# cowsynth_teensy_breakout_revA.net
KiCad netlist of a schematic drawn in EAGLE
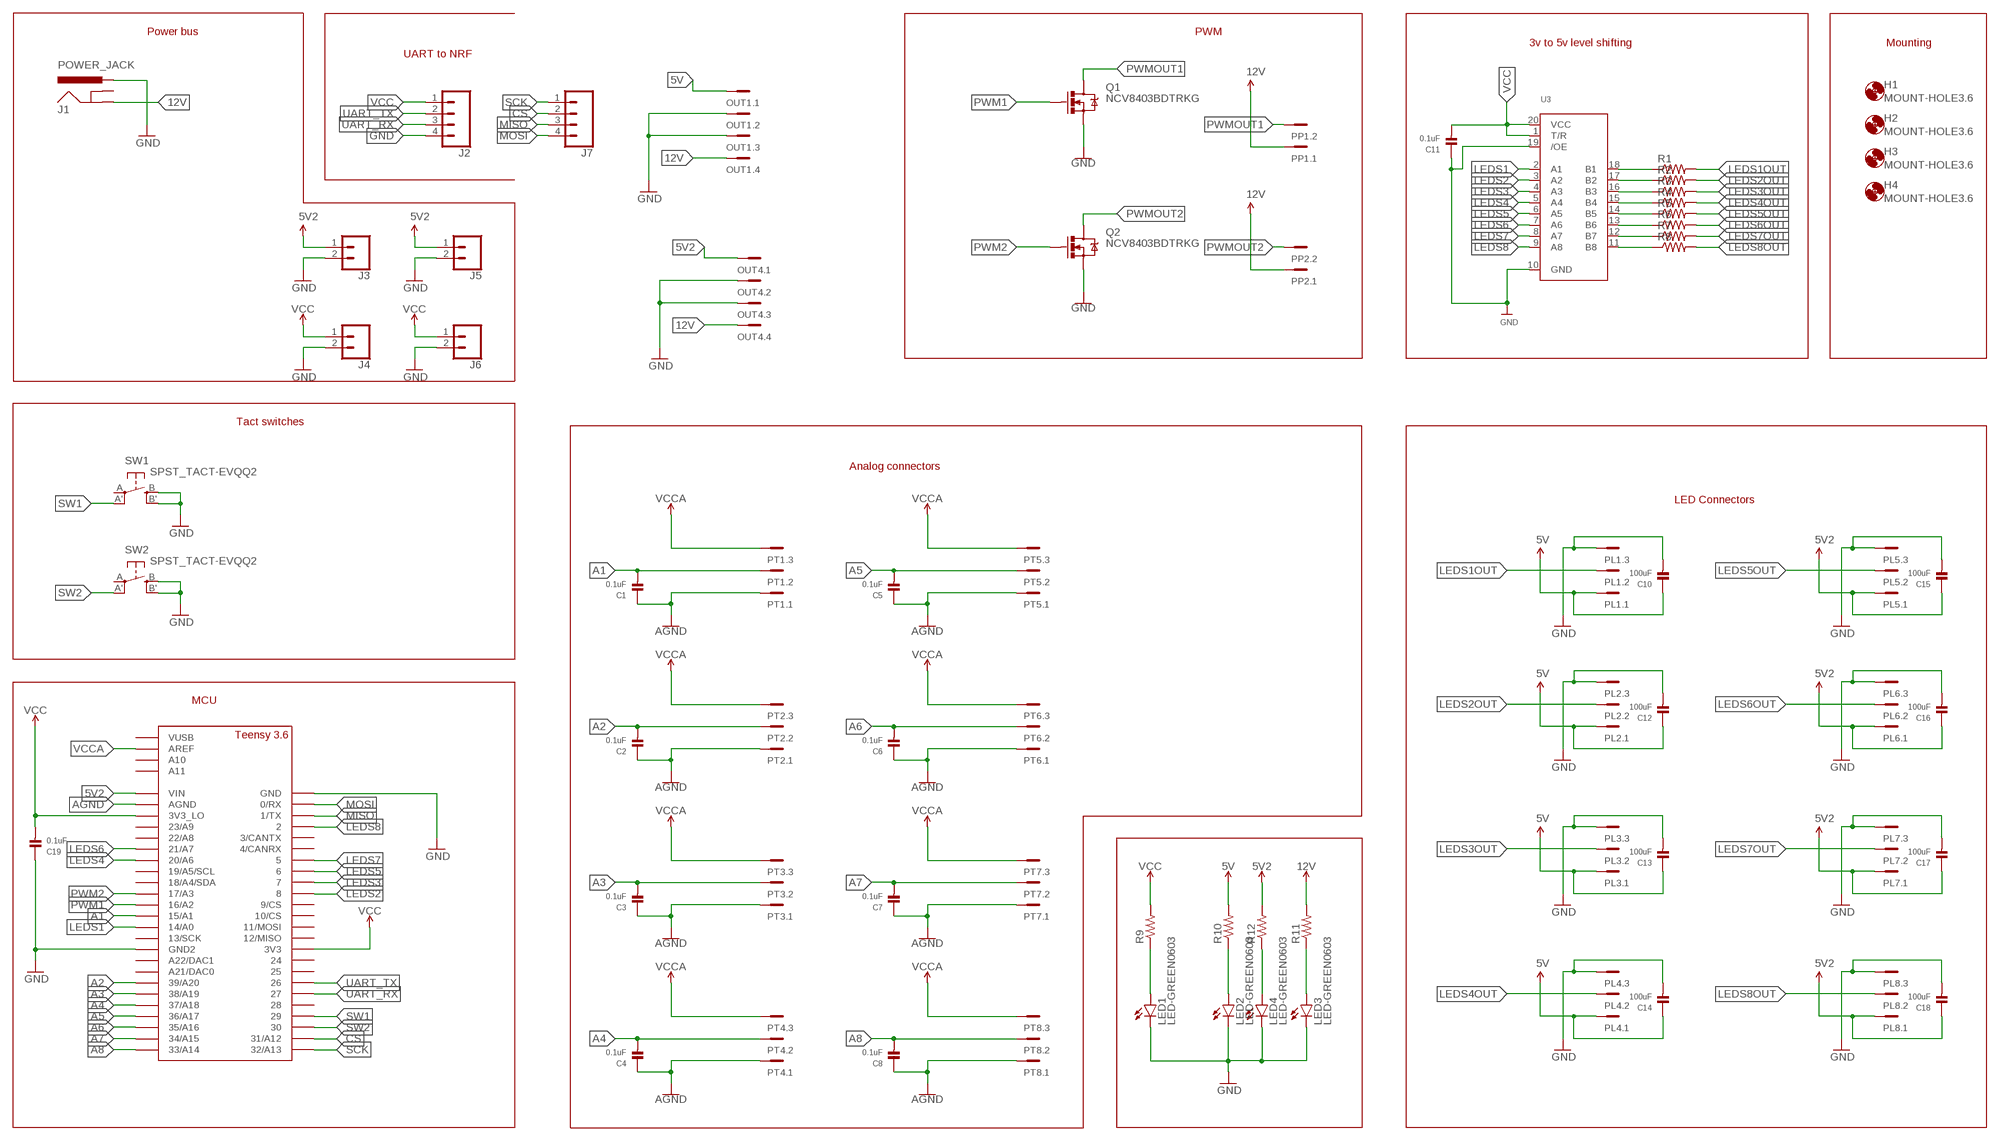
[diagram p0: schematic, sheet 1]

(export (version "E")
  (design (tool "Eeschema 10.0.6"))
  (components
    (comp (ref "C1")
      (value "0.1uF")
      (footprint "eagle-import:0603")
      (libsource (lib "eagle-import") (part "CAP_CERAMIC0603"))
    )
    (comp (ref "C2")
      (value "0.1uF")
      (footprint "eagle-import:0603")
      (libsource (lib "eagle-import") (part "CAP_CERAMIC0603"))
    )
    (comp (ref "C3")
      (value "0.1uF")
      (footprint "eagle-import:0603")
      (libsource (lib "eagle-import") (part "CAP_CERAMIC0603"))
    )
    (comp (ref "C4")
      (value "0.1uF")
      (footprint "eagle-import:0603")
      (libsource (lib "eagle-import") (part "CAP_CERAMIC0603"))
    )
    (comp (ref "C5")
      (value "0.1uF")
      (footprint "eagle-import:0603")
      (libsource (lib "eagle-import") (part "CAP_CERAMIC0603"))
    )
    (comp (ref "C6")
      (value "0.1uF")
      (footprint "eagle-import:0603")
      (libsource (lib "eagle-import") (part "CAP_CERAMIC0603"))
    )
    (comp (ref "C7")
      (value "0.1uF")
      (footprint "eagle-import:0603")
      (libsource (lib "eagle-import") (part "CAP_CERAMIC0603"))
    )
    (comp (ref "C8")
      (value "0.1uF")
      (footprint "eagle-import:0603")
      (libsource (lib "eagle-import") (part "CAP_CERAMIC0603"))
    )
    (comp (ref "C10")
      (value "100uF")
      (footprint "eagle-import:1206")
      (libsource (lib "eagle-import") (part "CAP_CERAMIC1206"))
    )
    (comp (ref "C11")
      (value "0.1uF")
      (footprint "eagle-import:0603")
      (libsource (lib "eagle-import") (part "CAP_CERAMIC0603"))
    )
    (comp (ref "C12")
      (value "100uF")
      (footprint "eagle-import:1206")
      (libsource (lib "eagle-import") (part "CAP_CERAMIC1206"))
    )
    (comp (ref "C13")
      (value "100uF")
      (footprint "eagle-import:1206")
      (libsource (lib "eagle-import") (part "CAP_CERAMIC1206"))
    )
    (comp (ref "C14")
      (value "100uF")
      (footprint "eagle-import:1206")
      (libsource (lib "eagle-import") (part "CAP_CERAMIC1206"))
    )
    (comp (ref "C15")
      (value "100uF")
      (footprint "eagle-import:1206")
      (libsource (lib "eagle-import") (part "CAP_CERAMIC1206"))
    )
    (comp (ref "C16")
      (value "100uF")
      (footprint "eagle-import:1206")
      (libsource (lib "eagle-import") (part "CAP_CERAMIC1206"))
    )
    (comp (ref "C17")
      (value "100uF")
      (footprint "eagle-import:1206")
      (libsource (lib "eagle-import") (part "CAP_CERAMIC1206"))
    )
    (comp (ref "C18")
      (value "100uF")
      (footprint "eagle-import:1206")
      (libsource (lib "eagle-import") (part "CAP_CERAMIC1206"))
    )
    (comp (ref "C19")
      (value "0.1uF")
      (footprint "eagle-import:0603")
      (libsource (lib "eagle-import") (part "CAP_CERAMIC0603"))
    )
    (comp (ref "H1")
      (value "MOUNT-HOLE3.6")
      (footprint "eagle-import:3,6")
      (libsource (lib "eagle-import") (part "MOUNT-HOLE3.6"))
    )
    (comp (ref "H2")
      (value "MOUNT-HOLE3.6")
      (footprint "eagle-import:3,6")
      (libsource (lib "eagle-import") (part "MOUNT-HOLE3.6"))
    )
    (comp (ref "H3")
      (value "MOUNT-HOLE3.6")
      (footprint "eagle-import:3,6")
      (libsource (lib "eagle-import") (part "MOUNT-HOLE3.6"))
    )
    (comp (ref "H4")
      (value "MOUNT-HOLE3.6")
      (footprint "eagle-import:3,6")
      (libsource (lib "eagle-import") (part "MOUNT-HOLE3.6"))
    )
    (comp (ref "J1")
      (value "POWER_JACK")
      (footprint "eagle-import:POWER_JACK_PTH")
      (libsource (lib "eagle-import") (part "POWER_JACK"))
    )
    (comp (ref "J2")
      (value "CONN_04")
      (footprint "eagle-import:1X04")
      (libsource (lib "eagle-import") (part "CONN_04"))
    )
    (comp (ref "J3")
      (value "CONN_02")
      (footprint "eagle-import:1X02")
      (libsource (lib "eagle-import") (part "CONN_02"))
    )
    (comp (ref "J4")
      (value "CONN_02")
      (footprint "eagle-import:1X02")
      (libsource (lib "eagle-import") (part "CONN_02"))
    )
    (comp (ref "J5")
      (value "CONN_02")
      (footprint "eagle-import:1X02")
      (libsource (lib "eagle-import") (part "CONN_02"))
    )
    (comp (ref "J6")
      (value "CONN_02")
      (footprint "eagle-import:1X02")
      (libsource (lib "eagle-import") (part "CONN_02"))
    )
    (comp (ref "J7")
      (value "CONN_04")
      (footprint "eagle-import:1X04")
      (libsource (lib "eagle-import") (part "CONN_04"))
    )
    (comp (ref "LED1")
      (value "LED-GREEN0603")
      (footprint "eagle-import:0603-GREEN")
      (libsource (lib "eagle-import") (part "LED-GREEN0603"))
    )
    (comp (ref "LED2")
      (value "LED-GREEN0603")
      (footprint "eagle-import:0603-GREEN")
      (libsource (lib "eagle-import") (part "LED-GREEN0603"))
    )
    (comp (ref "LED3")
      (value "LED-GREEN0603")
      (footprint "eagle-import:0603-GREEN")
      (libsource (lib "eagle-import") (part "LED-GREEN0603"))
    )
    (comp (ref "LED4")
      (value "LED-GREEN0603")
      (footprint "eagle-import:0603-GREEN")
      (libsource (lib "eagle-import") (part "LED-GREEN0603"))
    )
    (comp (ref "OUT1")
      (value "MC4")
      (footprint "eagle-import:MC4")
      (libsource (lib "eagle-import") (part "MC4"))
    )
    (comp (ref "OUT4")
      (value "MC4")
      (footprint "eagle-import:MC4")
      (libsource (lib "eagle-import") (part "MC4"))
    )
    (comp (ref "PL1")
      (value "MC3")
      (footprint "eagle-import:MC3")
      (libsource (lib "eagle-import") (part "MC3"))
    )
    (comp (ref "PL2")
      (value "MC3")
      (footprint "eagle-import:MC3")
      (libsource (lib "eagle-import") (part "MC3"))
    )
    (comp (ref "PL3")
      (value "MC3")
      (footprint "eagle-import:MC3")
      (libsource (lib "eagle-import") (part "MC3"))
    )
    (comp (ref "PL4")
      (value "MC3")
      (footprint "eagle-import:MC3")
      (libsource (lib "eagle-import") (part "MC3"))
    )
    (comp (ref "PL5")
      (value "MC3")
      (footprint "eagle-import:MC3")
      (libsource (lib "eagle-import") (part "MC3"))
    )
    (comp (ref "PL6")
      (value "MC3")
      (footprint "eagle-import:MC3")
      (libsource (lib "eagle-import") (part "MC3"))
    )
    (comp (ref "PL7")
      (value "MC3")
      (footprint "eagle-import:MC3")
      (libsource (lib "eagle-import") (part "MC3"))
    )
    (comp (ref "PL8")
      (value "MC3")
      (footprint "eagle-import:MC3")
      (libsource (lib "eagle-import") (part "MC3"))
    )
    (comp (ref "PP1")
      (value "MC2")
      (footprint "eagle-import:MC2")
      (libsource (lib "eagle-import") (part "MC2"))
    )
    (comp (ref "PP2")
      (value "MC2")
      (footprint "eagle-import:MC2")
      (libsource (lib "eagle-import") (part "MC2"))
    )
    (comp (ref "PT1")
      (value "MC3")
      (footprint "eagle-import:MC3")
      (libsource (lib "eagle-import") (part "MC3"))
    )
    (comp (ref "PT2")
      (value "MC3")
      (footprint "eagle-import:MC3")
      (libsource (lib "eagle-import") (part "MC3"))
    )
    (comp (ref "PT3")
      (value "MC3")
      (footprint "eagle-import:MC3")
      (libsource (lib "eagle-import") (part "MC3"))
    )
    (comp (ref "PT4")
      (value "MC3")
      (footprint "eagle-import:MC3")
      (libsource (lib "eagle-import") (part "MC3"))
    )
    (comp (ref "PT5")
      (value "MC3")
      (footprint "eagle-import:MC3")
      (libsource (lib "eagle-import") (part "MC3"))
    )
    (comp (ref "PT6")
      (value "MC3")
      (footprint "eagle-import:MC3")
      (libsource (lib "eagle-import") (part "MC3"))
    )
    (comp (ref "PT7")
      (value "MC3")
      (footprint "eagle-import:MC3")
      (libsource (lib "eagle-import") (part "MC3"))
    )
    (comp (ref "PT8")
      (value "MC3")
      (footprint "eagle-import:MC3")
      (libsource (lib "eagle-import") (part "MC3"))
    )
    (comp (ref "Q1")
      (value "NCV8403BDTRKG")
      (footprint "eagle-import:DPAK")
      (libsource (lib "eagle-import") (part "MOSFET-NCHANNELFDD8780"))
    )
    (comp (ref "Q2")
      (value "NCV8403BDTRKG")
      (footprint "eagle-import:DPAK")
      (libsource (lib "eagle-import") (part "MOSFET-NCHANNELFDD8780"))
    )
    (comp (ref "R1")
      (value "R-US_R0603")
      (footprint "eagle-import:R0603")
      (libsource (lib "eagle-import") (part "R-US_R0603"))
    )
    (comp (ref "R2")
      (value "R-US_R0603")
      (footprint "eagle-import:R0603")
      (libsource (lib "eagle-import") (part "R-US_R0603"))
    )
    (comp (ref "R3")
      (value "R-US_R0603")
      (footprint "eagle-import:R0603")
      (libsource (lib "eagle-import") (part "R-US_R0603"))
    )
    (comp (ref "R4")
      (value "R-US_R0603")
      (footprint "eagle-import:R0603")
      (libsource (lib "eagle-import") (part "R-US_R0603"))
    )
    (comp (ref "R5")
      (value "R-US_R0603")
      (footprint "eagle-import:R0603")
      (libsource (lib "eagle-import") (part "R-US_R0603"))
    )
    (comp (ref "R6")
      (value "R-US_R0603")
      (footprint "eagle-import:R0603")
      (libsource (lib "eagle-import") (part "R-US_R0603"))
    )
    (comp (ref "R7")
      (value "R-US_R0603")
      (footprint "eagle-import:R0603")
      (libsource (lib "eagle-import") (part "R-US_R0603"))
    )
    (comp (ref "R8")
      (value "R-US_R0603")
      (footprint "eagle-import:R0603")
      (libsource (lib "eagle-import") (part "R-US_R0603"))
    )
    (comp (ref "R9")
      (value "R-US_R0603")
      (footprint "eagle-import:R0603")
      (libsource (lib "eagle-import") (part "R-US_R0603"))
    )
    (comp (ref "R10")
      (value "R-US_R0603")
      (footprint "eagle-import:R0603")
      (libsource (lib "eagle-import") (part "R-US_R0603"))
    )
    (comp (ref "R11")
      (value "R-US_R0603")
      (footprint "eagle-import:R0603")
      (libsource (lib "eagle-import") (part "R-US_R0603"))
    )
    (comp (ref "R12")
      (value "R-US_R0603")
      (footprint "eagle-import:R0603")
      (libsource (lib "eagle-import") (part "R-US_R0603"))
    )
    (comp (ref "SW1")
      (value "SPST_TACT-EVQQ2")
      (footprint "eagle-import:EVQ-Q2")
      (libsource (lib "eagle-import") (part "SPST_TACT-EVQQ2"))
    )
    (comp (ref "SW2")
      (value "SPST_TACT-EVQQ2")
      (footprint "eagle-import:EVQ-Q2")
      (libsource (lib "eagle-import") (part "SPST_TACT-EVQQ2"))
    )
    (comp (ref "U$1")
      (value "TEENSY_3.5/3.6_BASIC")
      (footprint "eagle-import:TEENSY_3.5_3.6_BASIC")
      (libsource (lib "eagle-import") (part "TEENSY_3.5/3.6_BASIC"))
    )
    (comp (ref "U3")
      (value "74LCX245")
      (footprint "eagle-import:TSSOP20")
      (libsource (lib "eagle-import") (part "74LCX245"))
    )
  )
  (nets
    (net (code "1") (name "5V") (class "Default")
      (node (ref "C10") (pin "1") (pinfunction "P$1_1") (pintype "passive"))
      (node (ref "C12") (pin "1") (pinfunction "P$1_1") (pintype "passive"))
      (node (ref "C13") (pin "1") (pinfunction "P$1_1") (pintype "passive"))
      (node (ref "C14") (pin "1") (pinfunction "P$1_1") (pintype "passive"))
      (node (ref "OUT1") (pin "1") (pinfunction "SK_1") (pintype "passive"))
      (node (ref "PL1") (pin "1") (pinfunction "SK_1") (pintype "passive"))
      (node (ref "PL2") (pin "1") (pinfunction "SK_1") (pintype "passive"))
      (node (ref "PL3") (pin "1") (pinfunction "SK_1") (pintype "passive"))
      (node (ref "PL4") (pin "1") (pinfunction "SK_1") (pintype "passive"))
      (node (ref "R10") (pin "2") (pinfunction "2_2") (pintype "passive"))
    )
    (net (code "2") (name "5V2") (class "Default")
      (node (ref "C15") (pin "1") (pinfunction "P$1_1") (pintype "passive"))
      (node (ref "C16") (pin "1") (pinfunction "P$1_1") (pintype "passive"))
      (node (ref "C17") (pin "1") (pinfunction "P$1_1") (pintype "passive"))
      (node (ref "C18") (pin "1") (pinfunction "P$1_1") (pintype "passive"))
      (node (ref "J3") (pin "1") (pinfunction "1_1") (pintype "passive"))
      (node (ref "J5") (pin "1") (pinfunction "1_1") (pintype "passive"))
      (node (ref "OUT4") (pin "1") (pinfunction "SK_1") (pintype "passive"))
      (node (ref "PL5") (pin "1") (pinfunction "SK_1") (pintype "passive"))
      (node (ref "PL6") (pin "1") (pinfunction "SK_1") (pintype "passive"))
      (node (ref "PL7") (pin "1") (pinfunction "SK_1") (pintype "passive"))
      (node (ref "PL8") (pin "1") (pinfunction "SK_1") (pintype "passive"))
      (node (ref "R12") (pin "2") (pinfunction "2_2") (pintype "passive"))
      (node (ref "U$1") (pin "VIN") (pinfunction "VIN_VIN") (pintype "bidirectional"))
    )
    (net (code "3") (name "12V") (class "Default")
      (node (ref "J1") (pin "GND") (pinfunction "GND_GND") (pintype "bidirectional"))
      (node (ref "OUT1") (pin "4") (pinfunction "SK_4") (pintype "passive"))
      (node (ref "OUT4") (pin "4") (pinfunction "SK_4") (pintype "passive"))
      (node (ref "PP1") (pin "1") (pinfunction "SK_1") (pintype "passive"))
      (node (ref "PP2") (pin "1") (pinfunction "SK_1") (pintype "passive"))
      (node (ref "R11") (pin "2") (pinfunction "2_2") (pintype "passive"))
    )
    (net (code "4") (name "A1") (class "Default")
      (node (ref "C1") (pin "2") (pinfunction "P$2_2") (pintype "passive"))
      (node (ref "PT1") (pin "2") (pinfunction "SK_2") (pintype "passive"))
      (node (ref "U$1") (pin "15/A1") (pinfunction "15/A1_15/A1") (pintype "bidirectional"))
    )
    (net (code "5") (name "A2") (class "Default")
      (node (ref "C2") (pin "2") (pinfunction "P$2_2") (pintype "passive"))
      (node (ref "PT2") (pin "2") (pinfunction "SK_2") (pintype "passive"))
      (node (ref "U$1") (pin "39/A20") (pinfunction "39/A20_39/A20") (pintype "bidirectional"))
    )
    (net (code "6") (name "A3") (class "Default")
      (node (ref "C3") (pin "2") (pinfunction "P$2_2") (pintype "passive"))
      (node (ref "PT3") (pin "2") (pinfunction "SK_2") (pintype "passive"))
      (node (ref "U$1") (pin "38/A19") (pinfunction "38/A19_38/A19") (pintype "bidirectional"))
    )
    (net (code "7") (name "A4") (class "Default")
      (node (ref "C4") (pin "2") (pinfunction "P$2_2") (pintype "passive"))
      (node (ref "PT4") (pin "2") (pinfunction "SK_2") (pintype "passive"))
      (node (ref "U$1") (pin "37/A18") (pinfunction "37/A18_37/A18") (pintype "bidirectional"))
    )
    (net (code "8") (name "A5") (class "Default")
      (node (ref "C5") (pin "2") (pinfunction "P$2_2") (pintype "passive"))
      (node (ref "PT5") (pin "2") (pinfunction "SK_2") (pintype "passive"))
      (node (ref "U$1") (pin "36/A17") (pinfunction "36/A17_36/A17") (pintype "bidirectional"))
    )
    (net (code "9") (name "A6") (class "Default")
      (node (ref "C6") (pin "2") (pinfunction "P$2_2") (pintype "passive"))
      (node (ref "PT6") (pin "2") (pinfunction "SK_2") (pintype "passive"))
      (node (ref "U$1") (pin "35/A16") (pinfunction "35/A16_35/A16") (pintype "bidirectional"))
    )
    (net (code "10") (name "A7") (class "Default")
      (node (ref "C7") (pin "2") (pinfunction "P$2_2") (pintype "passive"))
      (node (ref "PT7") (pin "2") (pinfunction "SK_2") (pintype "passive"))
      (node (ref "U$1") (pin "34/A15") (pinfunction "34/A15_34/A15") (pintype "bidirectional"))
    )
    (net (code "11") (name "A8") (class "Default")
      (node (ref "C8") (pin "2") (pinfunction "P$2_2") (pintype "passive"))
      (node (ref "PT8") (pin "2") (pinfunction "SK_2") (pintype "passive"))
      (node (ref "U$1") (pin "33/A14") (pinfunction "33/A14_33/A14") (pintype "bidirectional"))
    )
    (net (code "12") (name "AGND") (class "Default")
      (node (ref "C1") (pin "1") (pinfunction "P$1_1") (pintype "passive"))
      (node (ref "C2") (pin "1") (pinfunction "P$1_1") (pintype "passive"))
      (node (ref "C3") (pin "1") (pinfunction "P$1_1") (pintype "passive"))
      (node (ref "C4") (pin "1") (pinfunction "P$1_1") (pintype "passive"))
      (node (ref "C5") (pin "1") (pinfunction "P$1_1") (pintype "passive"))
      (node (ref "C6") (pin "1") (pinfunction "P$1_1") (pintype "passive"))
      (node (ref "C7") (pin "1") (pinfunction "P$1_1") (pintype "passive"))
      (node (ref "C8") (pin "1") (pinfunction "P$1_1") (pintype "passive"))
      (node (ref "PT1") (pin "1") (pinfunction "SK_1") (pintype "passive"))
      (node (ref "PT2") (pin "1") (pinfunction "SK_1") (pintype "passive"))
      (node (ref "PT3") (pin "1") (pinfunction "SK_1") (pintype "passive"))
      (node (ref "PT4") (pin "1") (pinfunction "SK_1") (pintype "passive"))
      (node (ref "PT5") (pin "1") (pinfunction "SK_1") (pintype "passive"))
      (node (ref "PT6") (pin "1") (pinfunction "SK_1") (pintype "passive"))
      (node (ref "PT7") (pin "1") (pinfunction "SK_1") (pintype "passive"))
      (node (ref "PT8") (pin "1") (pinfunction "SK_1") (pintype "passive"))
      (node (ref "U$1") (pin "AGND") (pinfunction "AGND_AGND") (pintype "bidirectional"))
    )
    (net (code "13") (name "CS") (class "Default")
      (node (ref "J7") (pin "2") (pinfunction "2_2") (pintype "passive"))
      (node (ref "U$1") (pin "31/A12") (pinfunction "31/A12_31/A12") (pintype "bidirectional"))
    )
    (net (code "14") (name "GND") (class "Default")
      (node (ref "C10") (pin "2") (pinfunction "P$2_2") (pintype "passive"))
      (node (ref "C11") (pin "1") (pinfunction "P$1_1") (pintype "passive"))
      (node (ref "C12") (pin "2") (pinfunction "P$2_2") (pintype "passive"))
      (node (ref "C13") (pin "2") (pinfunction "P$2_2") (pintype "passive"))
      (node (ref "C14") (pin "2") (pinfunction "P$2_2") (pintype "passive"))
      (node (ref "C15") (pin "2") (pinfunction "P$2_2") (pintype "passive"))
      (node (ref "C16") (pin "2") (pinfunction "P$2_2") (pintype "passive"))
      (node (ref "C17") (pin "2") (pinfunction "P$2_2") (pintype "passive"))
      (node (ref "C18") (pin "2") (pinfunction "P$2_2") (pintype "passive"))
      (node (ref "C19") (pin "1") (pinfunction "P$1_1") (pintype "passive"))
      (node (ref "J1") (pin "PWR") (pinfunction "PWR_PWR") (pintype "bidirectional"))
      (node (ref "J2") (pin "4") (pinfunction "4_4") (pintype "passive"))
      (node (ref "J3") (pin "2") (pinfunction "2_2") (pintype "passive"))
      (node (ref "J4") (pin "2") (pinfunction "2_2") (pintype "passive"))
      (node (ref "J5") (pin "2") (pinfunction "2_2") (pintype "passive"))
      (node (ref "J6") (pin "2") (pinfunction "2_2") (pintype "passive"))
      (node (ref "LED1") (pin "C") (pinfunction "C_C") (pintype "passive"))
      (node (ref "LED2") (pin "C") (pinfunction "C_C") (pintype "passive"))
      (node (ref "LED3") (pin "C") (pinfunction "C_C") (pintype "passive"))
      (node (ref "LED4") (pin "C") (pinfunction "C_C") (pintype "passive"))
      (node (ref "OUT1") (pin "2") (pinfunction "SK_2") (pintype "passive"))
      (node (ref "OUT1") (pin "3") (pinfunction "SK_3") (pintype "passive"))
      (node (ref "OUT4") (pin "2") (pinfunction "SK_2") (pintype "passive"))
      (node (ref "OUT4") (pin "3") (pinfunction "SK_3") (pintype "passive"))
      (node (ref "PL1") (pin "3") (pinfunction "SK_3") (pintype "passive"))
      (node (ref "PL2") (pin "3") (pinfunction "SK_3") (pintype "passive"))
      (node (ref "PL3") (pin "3") (pinfunction "SK_3") (pintype "passive"))
      (node (ref "PL4") (pin "3") (pinfunction "SK_3") (pintype "passive"))
      (node (ref "PL5") (pin "3") (pinfunction "SK_3") (pintype "passive"))
      (node (ref "PL6") (pin "3") (pinfunction "SK_3") (pintype "passive"))
      (node (ref "PL7") (pin "3") (pinfunction "SK_3") (pintype "passive"))
      (node (ref "PL8") (pin "3") (pinfunction "SK_3") (pintype "passive"))
      (node (ref "Q1") (pin "3") (pinfunction "S_3") (pintype "passive"))
      (node (ref "Q2") (pin "3") (pinfunction "S_3") (pintype "passive"))
      (node (ref "SW1") (pin "B") (pinfunction "S_B") (pintype "passive"))
      (node (ref "SW1") (pin "B'") (pinfunction "S1_B'") (pintype "passive"))
      (node (ref "SW2") (pin "B") (pinfunction "S_B") (pintype "passive"))
      (node (ref "SW2") (pin "B'") (pinfunction "S1_B'") (pintype "passive"))
      (node (ref "U$1") (pin "GND") (pinfunction "GND_GND") (pintype "bidirectional"))
      (node (ref "U$1") (pin "GND2") (pinfunction "GND2_GND2") (pintype "bidirectional"))
      (node (ref "U3") (pin "10") (pinfunction "GND_10") (pintype "bidirectional"))
      (node (ref "U3") (pin "19") (pinfunction "/OE_19") (pintype "bidirectional"))
    )
    (net (code "15") (name "LEDS1") (class "Default")
      (node (ref "U$1") (pin "14/A0") (pinfunction "14/A0_14/A0") (pintype "bidirectional"))
      (node (ref "U3") (pin "2") (pinfunction "A1_2") (pintype "bidirectional"))
    )
    (net (code "16") (name "LEDS1OUT") (class "Default")
      (node (ref "PL1") (pin "2") (pinfunction "SK_2") (pintype "passive"))
      (node (ref "R1") (pin "2") (pinfunction "2_2") (pintype "passive"))
    )
    (net (code "17") (name "LEDS2") (class "Default")
      (node (ref "U$1") (pin "8") (pinfunction "8_8") (pintype "bidirectional"))
      (node (ref "U3") (pin "3") (pinfunction "A2_3") (pintype "bidirectional"))
    )
    (net (code "18") (name "LEDS2OUT") (class "Default")
      (node (ref "PL2") (pin "2") (pinfunction "SK_2") (pintype "passive"))
      (node (ref "R2") (pin "2") (pinfunction "2_2") (pintype "passive"))
    )
    (net (code "19") (name "LEDS3") (class "Default")
      (node (ref "U$1") (pin "7") (pinfunction "7_7") (pintype "bidirectional"))
      (node (ref "U3") (pin "4") (pinfunction "A3_4") (pintype "bidirectional"))
    )
    (net (code "20") (name "LEDS3OUT") (class "Default")
      (node (ref "PL3") (pin "2") (pinfunction "SK_2") (pintype "passive"))
      (node (ref "R3") (pin "2") (pinfunction "2_2") (pintype "passive"))
    )
    (net (code "21") (name "LEDS4") (class "Default")
      (node (ref "U$1") (pin "20/A6") (pinfunction "20/A6_20/A6") (pintype "bidirectional"))
      (node (ref "U3") (pin "5") (pinfunction "A4_5") (pintype "bidirectional"))
    )
    (net (code "22") (name "LEDS4OUT") (class "Default")
      (node (ref "PL4") (pin "2") (pinfunction "SK_2") (pintype "passive"))
      (node (ref "R4") (pin "2") (pinfunction "2_2") (pintype "passive"))
    )
    (net (code "23") (name "LEDS5") (class "Default")
      (node (ref "U$1") (pin "6") (pinfunction "6_6") (pintype "bidirectional"))
      (node (ref "U3") (pin "6") (pinfunction "A5_6") (pintype "bidirectional"))
    )
    (net (code "24") (name "LEDS5OUT") (class "Default")
      (node (ref "PL5") (pin "2") (pinfunction "SK_2") (pintype "passive"))
      (node (ref "R5") (pin "2") (pinfunction "2_2") (pintype "passive"))
    )
    (net (code "25") (name "LEDS6") (class "Default")
      (node (ref "U$1") (pin "21/A7") (pinfunction "21/A7_21/A7") (pintype "bidirectional"))
      (node (ref "U3") (pin "7") (pinfunction "A6_7") (pintype "bidirectional"))
    )
    (net (code "26") (name "LEDS6OUT") (class "Default")
      (node (ref "PL6") (pin "2") (pinfunction "SK_2") (pintype "passive"))
      (node (ref "R6") (pin "2") (pinfunction "2_2") (pintype "passive"))
    )
    (net (code "27") (name "LEDS7") (class "Default")
      (node (ref "U$1") (pin "5") (pinfunction "5_5") (pintype "bidirectional"))
      (node (ref "U3") (pin "8") (pinfunction "A7_8") (pintype "bidirectional"))
    )
    (net (code "28") (name "LEDS7OUT") (class "Default")
      (node (ref "PL7") (pin "2") (pinfunction "SK_2") (pintype "passive"))
      (node (ref "R7") (pin "2") (pinfunction "2_2") (pintype "passive"))
    )
    (net (code "29") (name "LEDS8") (class "Default")
      (node (ref "U$1") (pin "2") (pinfunction "2_2") (pintype "bidirectional"))
      (node (ref "U3") (pin "9") (pinfunction "A8_9") (pintype "bidirectional"))
    )
    (net (code "30") (name "LEDS8OUT") (class "Default")
      (node (ref "PL8") (pin "2") (pinfunction "SK_2") (pintype "passive"))
      (node (ref "R8") (pin "2") (pinfunction "2_2") (pintype "passive"))
    )
    (net (code "31") (name "MISO") (class "Default")
      (node (ref "J7") (pin "3") (pinfunction "3_3") (pintype "passive"))
      (node (ref "U$1") (pin "1/TX") (pinfunction "1/TX_1/TX") (pintype "bidirectional"))
    )
    (net (code "32") (name "MOSI") (class "Default")
      (node (ref "J7") (pin "4") (pinfunction "4_4") (pintype "passive"))
      (node (ref "U$1") (pin "0/RX") (pinfunction "0/RX_0/RX") (pintype "bidirectional"))
    )
    (net (code "33") (name "Net-(LED1-PadA)") (class "Default")
      (node (ref "LED1") (pin "A") (pinfunction "A_A") (pintype "passive"))
      (node (ref "R9") (pin "1") (pinfunction "1_1") (pintype "passive"))
    )
    (net (code "34") (name "Net-(LED2-PadA)") (class "Default")
      (node (ref "LED2") (pin "A") (pinfunction "A_A") (pintype "passive"))
      (node (ref "R10") (pin "1") (pinfunction "1_1") (pintype "passive"))
    )
    (net (code "35") (name "Net-(LED3-PadA)") (class "Default")
      (node (ref "LED3") (pin "A") (pinfunction "A_A") (pintype "passive"))
      (node (ref "R11") (pin "1") (pinfunction "1_1") (pintype "passive"))
    )
    (net (code "36") (name "Net-(LED4-PadA)") (class "Default")
      (node (ref "LED4") (pin "A") (pinfunction "A_A") (pintype "passive"))
      (node (ref "R12") (pin "1") (pinfunction "1_1") (pintype "passive"))
    )
    (net (code "37") (name "Net-(U3-B1)") (class "Default")
      (node (ref "R1") (pin "1") (pinfunction "1_1") (pintype "passive"))
      (node (ref "U3") (pin "18") (pinfunction "B1_18") (pintype "bidirectional"))
    )
    (net (code "38") (name "Net-(U3-B2)") (class "Default")
      (node (ref "R2") (pin "1") (pinfunction "1_1") (pintype "passive"))
      (node (ref "U3") (pin "17") (pinfunction "B2_17") (pintype "bidirectional"))
    )
    (net (code "39") (name "Net-(U3-B3)") (class "Default")
      (node (ref "R3") (pin "1") (pinfunction "1_1") (pintype "passive"))
      (node (ref "U3") (pin "16") (pinfunction "B3_16") (pintype "bidirectional"))
    )
    (net (code "40") (name "Net-(U3-B4)") (class "Default")
      (node (ref "R4") (pin "1") (pinfunction "1_1") (pintype "passive"))
      (node (ref "U3") (pin "15") (pinfunction "B4_15") (pintype "bidirectional"))
    )
    (net (code "41") (name "Net-(U3-B5)") (class "Default")
      (node (ref "R5") (pin "1") (pinfunction "1_1") (pintype "passive"))
      (node (ref "U3") (pin "14") (pinfunction "B5_14") (pintype "bidirectional"))
    )
    (net (code "42") (name "Net-(U3-B6)") (class "Default")
      (node (ref "R6") (pin "1") (pinfunction "1_1") (pintype "passive"))
      (node (ref "U3") (pin "13") (pinfunction "B6_13") (pintype "bidirectional"))
    )
    (net (code "43") (name "Net-(U3-B7)") (class "Default")
      (node (ref "R7") (pin "1") (pinfunction "1_1") (pintype "passive"))
      (node (ref "U3") (pin "12") (pinfunction "B7_12") (pintype "bidirectional"))
    )
    (net (code "44") (name "Net-(U3-B8)") (class "Default")
      (node (ref "R8") (pin "1") (pinfunction "1_1") (pintype "passive"))
      (node (ref "U3") (pin "11") (pinfunction "B8_11") (pintype "bidirectional"))
    )
    (net (code "45") (name "PWM1") (class "Default")
      (node (ref "Q1") (pin "1") (pinfunction "G_1") (pintype "passive"))
      (node (ref "U$1") (pin "16/A2") (pinfunction "16/A2_16/A2") (pintype "bidirectional"))
    )
    (net (code "46") (name "PWM2") (class "Default")
      (node (ref "Q2") (pin "1") (pinfunction "G_1") (pintype "passive"))
      (node (ref "U$1") (pin "17/A3") (pinfunction "17/A3_17/A3") (pintype "bidirectional"))
    )
    (net (code "47") (name "PWMOUT1") (class "Default")
      (node (ref "PP1") (pin "2") (pinfunction "SK_2") (pintype "passive"))
      (node (ref "Q1") (pin "4") (pinfunction "D_4") (pintype "passive"))
    )
    (net (code "48") (name "PWMOUT2") (class "Default")
      (node (ref "PP2") (pin "2") (pinfunction "SK_2") (pintype "passive"))
      (node (ref "Q2") (pin "4") (pinfunction "D_4") (pintype "passive"))
    )
    (net (code "49") (name "SCK") (class "Default")
      (node (ref "J7") (pin "1") (pinfunction "1_1") (pintype "passive"))
      (node (ref "U$1") (pin "32/A13") (pinfunction "32/A13_32/A13") (pintype "bidirectional"))
    )
    (net (code "50") (name "SW1") (class "Default")
      (node (ref "SW1") (pin "A'") (pinfunction "P1_A'") (pintype "passive"))
      (node (ref "U$1") (pin "29") (pinfunction "29_29") (pintype "bidirectional"))
    )
    (net (code "51") (name "SW2") (class "Default")
      (node (ref "SW2") (pin "A'") (pinfunction "P1_A'") (pintype "passive"))
      (node (ref "U$1") (pin "30") (pinfunction "30_30") (pintype "bidirectional"))
    )
    (net (code "52") (name "UART_RX") (class "Default")
      (node (ref "J2") (pin "3") (pinfunction "3_3") (pintype "passive"))
      (node (ref "U$1") (pin "27") (pinfunction "27_27") (pintype "bidirectional"))
    )
    (net (code "53") (name "UART_TX") (class "Default")
      (node (ref "J2") (pin "2") (pinfunction "2_2") (pintype "passive"))
      (node (ref "U$1") (pin "26") (pinfunction "26_26") (pintype "bidirectional"))
    )
    (net (code "54") (name "VCC") (class "Default")
      (node (ref "C11") (pin "2") (pinfunction "P$2_2") (pintype "passive"))
      (node (ref "C19") (pin "2") (pinfunction "P$2_2") (pintype "passive"))
      (node (ref "J2") (pin "1") (pinfunction "1_1") (pintype "passive"))
      (node (ref "J4") (pin "1") (pinfunction "1_1") (pintype "passive"))
      (node (ref "J6") (pin "1") (pinfunction "1_1") (pintype "passive"))
      (node (ref "R9") (pin "2") (pinfunction "2_2") (pintype "passive"))
      (node (ref "U$1") (pin "3V3") (pinfunction "3V3_3V3") (pintype "bidirectional"))
      (node (ref "U$1") (pin "3V3_LO") (pinfunction "3V3_LO_3V3_LO") (pintype "bidirectional"))
      (node (ref "U3") (pin "1") (pinfunction "T/R_1") (pintype "bidirectional"))
      (node (ref "U3") (pin "20") (pinfunction "VCC_20") (pintype "bidirectional"))
    )
    (net (code "55") (name "VCCA") (class "Default")
      (node (ref "PT1") (pin "3") (pinfunction "SK_3") (pintype "passive"))
      (node (ref "PT2") (pin "3") (pinfunction "SK_3") (pintype "passive"))
      (node (ref "PT3") (pin "3") (pinfunction "SK_3") (pintype "passive"))
      (node (ref "PT4") (pin "3") (pinfunction "SK_3") (pintype "passive"))
      (node (ref "PT5") (pin "3") (pinfunction "SK_3") (pintype "passive"))
      (node (ref "PT6") (pin "3") (pinfunction "SK_3") (pintype "passive"))
      (node (ref "PT7") (pin "3") (pinfunction "SK_3") (pintype "passive"))
      (node (ref "PT8") (pin "3") (pinfunction "SK_3") (pintype "passive"))
      (node (ref "U$1") (pin "AREF") (pinfunction "AREF_AREF") (pintype "bidirectional"))
    )
    (net (code "56") (name "unconnected-(J1-PadGNDBREAK)") (class "Default")
      (node (ref "J1") (pin "GNDBREAK") (pinfunction "GNDBREAK_GNDBREAK") (pintype "bidirectional"))
    )
    (net (code "57") (name "unconnected-(SW1-P-PadA)") (class "Default")
      (node (ref "SW1") (pin "A") (pinfunction "P_A") (pintype "passive"))
    )
    (net (code "58") (name "unconnected-(SW2-P-PadA)") (class "Default")
      (node (ref "SW2") (pin "A") (pinfunction "P_A") (pintype "passive"))
    )
    (net (code "59") (name "unconnected-(U$1-A21{slash}DAC0-Pad21{slash}DAC0)") (class "Default")
      (node (ref "U$1") (pin "21/DAC0") (pinfunction "A21/DAC0_21/DAC0") (pintype "bidirectional"))
    )
    (net (code "60") (name "unconnected-(U$1-Pad3{slash}CANTX)") (class "Default")
      (node (ref "U$1") (pin "3/CANTX") (pinfunction "3/CANTX_3/CANTX") (pintype "bidirectional"))
    )
    (net (code "61") (name "unconnected-(U$1-Pad4{slash}CANRX)") (class "Default")
      (node (ref "U$1") (pin "4/CANRX") (pinfunction "4/CANRX_4/CANRX") (pintype "bidirectional"))
    )
    (net (code "62") (name "unconnected-(U$1-Pad9{slash}CS)") (class "Default")
      (node (ref "U$1") (pin "9/CS") (pinfunction "9/CS_9/CS") (pintype "bidirectional"))
    )
    (net (code "63") (name "unconnected-(U$1-Pad10{slash}CS)") (class "Default")
      (node (ref "U$1") (pin "10/CS") (pinfunction "10/CS_10/CS") (pintype "bidirectional"))
    )
    (net (code "64") (name "unconnected-(U$1-Pad11{slash}MOSI)") (class "Default")
      (node (ref "U$1") (pin "11/MOSI") (pinfunction "11/MOSI_11/MOSI") (pintype "bidirectional"))
    )
    (net (code "65") (name "unconnected-(U$1-Pad12{slash}MISO)") (class "Default")
      (node (ref "U$1") (pin "12/MISO") (pinfunction "12/MISO_12/MISO") (pintype "bidirectional"))
    )
    (net (code "66") (name "unconnected-(U$1-Pad13{slash}SCK)") (class "Default")
      (node (ref "U$1") (pin "13/SCK") (pinfunction "13/SCK_13/SCK") (pintype "bidirectional"))
    )
    (net (code "67") (name "unconnected-(U$1-Pad18{slash}A4{slash}SDA)") (class "Default")
      (node (ref "U$1") (pin "18/A4/SDA") (pinfunction "18/A4/SDA_18/A4/SDA") (pintype "bidirectional"))
    )
    (net (code "68") (name "unconnected-(U$1-Pad19{slash}A5{slash}SCL)") (class "Default")
      (node (ref "U$1") (pin "19/A5/SCL") (pinfunction "19/A5/SCL_19/A5/SCL") (pintype "bidirectional"))
    )
    (net (code "69") (name "unconnected-(U$1-Pad22{slash}A8)") (class "Default")
      (node (ref "U$1") (pin "22/A8") (pinfunction "22/A8_22/A8") (pintype "bidirectional"))
    )
    (net (code "70") (name "unconnected-(U$1-Pad23{slash}A9)") (class "Default")
      (node (ref "U$1") (pin "23/A9") (pinfunction "23/A9_23/A9") (pintype "bidirectional"))
    )
    (net (code "71") (name "unconnected-(U$1-Pad24)") (class "Default")
      (node (ref "U$1") (pin "24") (pinfunction "24_24") (pintype "bidirectional"))
    )
    (net (code "72") (name "unconnected-(U$1-Pad25)") (class "Default")
      (node (ref "U$1") (pin "25") (pinfunction "25_25") (pintype "bidirectional"))
    )
    (net (code "73") (name "unconnected-(U$1-Pad28)") (class "Default")
      (node (ref "U$1") (pin "28") (pinfunction "28_28") (pintype "bidirectional"))
    )
    (net (code "74") (name "unconnected-(U$1-PadA10)") (class "Default")
      (node (ref "U$1") (pin "A10") (pinfunction "A10_A10") (pintype "bidirectional"))
    )
    (net (code "75") (name "unconnected-(U$1-PadA11)") (class "Default")
      (node (ref "U$1") (pin "A11") (pinfunction "A11_A11") (pintype "bidirectional"))
    )
    (net (code "76") (name "unconnected-(U$1-PadA22{slash}DAC1)") (class "Default")
      (node (ref "U$1") (pin "A22/DAC1") (pinfunction "A22/DAC1_A22/DAC1") (pintype "bidirectional"))
    )
    (net (code "77") (name "unconnected-(U$1-PadVUSB)") (class "Default")
      (node (ref "U$1") (pin "VUSB") (pinfunction "VUSB_VUSB") (pintype "bidirectional"))
    )
  )
)
